# PowerSwitch.net
KiCad netlist of a schematic drawn in Altium Designer
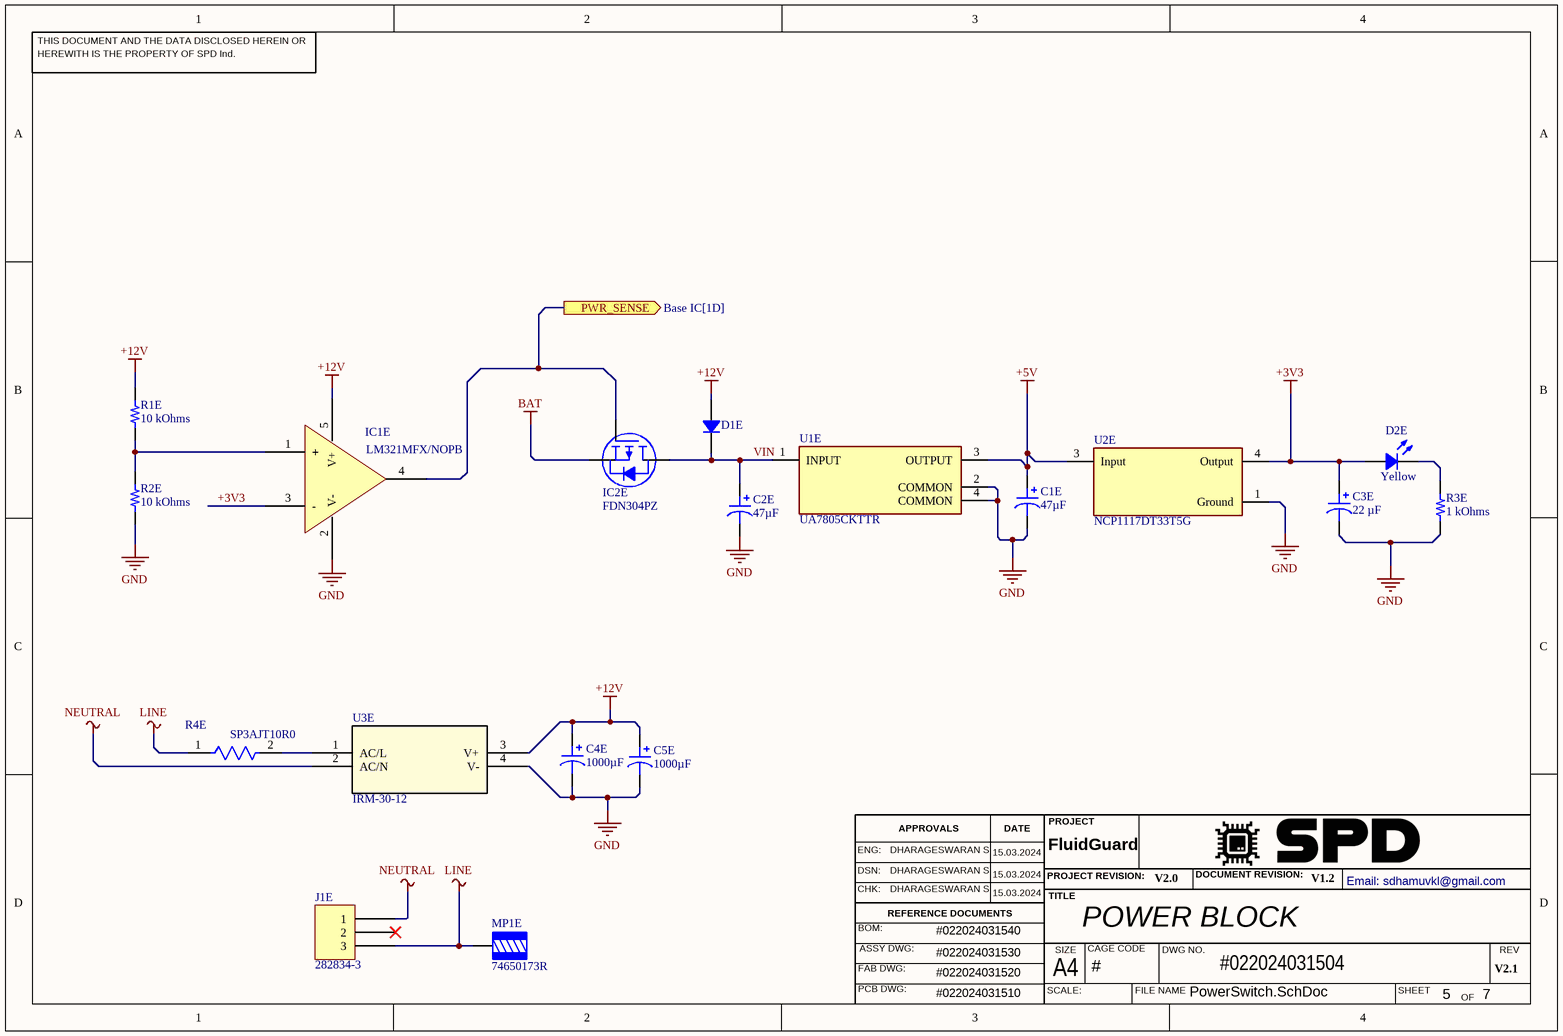
[diagram p0: PowerSwitch.SchDoc]

(export (version "E")
  (design (tool "Eeschema 10.0.6"))
  (components
    (comp (ref "C1E")
      (value "47µF")
      (footprint "CAP ALSMD 6.6MM H5.4MM")
      (description "CAP ALUM 47UF 20% 16V SMD")
      (fields
        (field (name "PART NUMBER") "EEE-HA1C470P")
        (field (name "MANUFACTURER") "Panasonic Electronic Components")
      )
      (libsource (lib "Postgres Altium Library - altium_library") (part "Polarised Capacitor"))
    )
    (comp (ref "C2E")
      (value "47µF")
      (footprint "CAP ALSMD 6.6MM H5.4MM")
      (description "CAP ALUM 47UF 20% 16V SMD")
      (fields
        (field (name "PART NUMBER") "EEE-HA1C470P")
        (field (name "MANUFACTURER") "Panasonic Electronic Components")
      )
      (libsource (lib "Postgres Altium Library - altium_library") (part "Polarised Capacitor"))
    )
    (comp (ref "C3E")
      (value "22 µF")
      (footprint "CAP POL 2917_7343")
      (description "CAP TANT 22UF 10% 10V 2917")
      (fields (field (name "PART NUMBER") "T491D226K010AT") (field (name "MANUFACTURER") "KEMET"))
      (libsource (lib "Postgres Altium Library - altium_library") (part "Polarised Capacitor"))
    )
    (comp (ref "C4E")
      (value "1000µF")
      (footprint "CAP TH ALUM ELEC D10.00mm S5.00mm H14.00mm")
      (description "CAP ALUM 1000UF 20% 16V RADIAL")
      (fields (field (name "PART NUMBER") "860020375017") (field (name "MANUFACTURER") "Würth Elektronik"))
      (libsource (lib "Postgres Altium Library - altium_library") (part "Polarised Capacitor"))
    )
    (comp (ref "C5E")
      (value "1000µF")
      (footprint "CAP TH ALUM ELEC D10.00mm S5.00mm H14.00mm")
      (description "CAP ALUM 1000UF 20% 16V RADIAL")
      (fields (field (name "PART NUMBER") "860020375017") (field (name "MANUFACTURER") "Würth Elektronik"))
      (libsource (lib "Postgres Altium Library - altium_library") (part "Polarised Capacitor"))
    )
    (comp (ref "D1E")
      (value "ES2A-13-F")
      (footprint "DO214AA SMB")
      (description "DIODE GEN PURP 50V 2A SMB")
      (fields (field (name "MANUFACTURER") "Diodes Incorporated"))
      (libsource (lib "Postgres Altium Library - altium_library") (part "Diode"))
    )
    (comp (ref "D2E")
      (value "Yellow")
      (footprint "LED 0402_1005 YELLOW")
      (description "LED YELLOW CLEAR 0402 SMD")
      (fields (field (name "PART NUMBER") "SM0402YC") (field (name "MANUFACTURER") "Bivar Inc."))
      (libsource (lib "Postgres Altium Library - altium_library") (part "LED"))
    )
    (comp (ref "IC1E")
      (value "LM321MFX/NOPB")
      (footprint "TI SOT-23-5 DBV")
      (description "IC OPAMP GP 1 CIRCUIT SOT23-5")
      (fields (field (name "MANUFACTURER") "Texas Instruments"))
      (libsource (lib "Postgres Altium Library - altium_library") (part "TI LM321"))
    )
    (comp (ref "IC2E")
      (value "FDN304PZ")
      (footprint "ON SEMI SOT-23-3")
      (description "MOSFET P-CH 20V 2.4A SSOT-3")
      (fields (field (name "MANUFACTURER") "ON Semiconductor"))
      (libsource (lib "Postgres Altium Library - altium_library") (part "ON SEMI MOSFET P-CH SOT-23-3"))
    )
    (comp (ref "J1E")
      (value "282834-3")
      (footprint "TE 282834-3")
      (description "TERM BLK 3P SIDE ENT 2.54MM PCB")
      (fields (field (name "VOLTAGE") "150V") (field (name "MANUFACTURER") "TE Connectivity AMP Connectors"))
      (libsource (lib "Postgres Altium Library - altium_library") (part "3 Pin"))
    )
    (comp (ref "MP1E")
      (value "74650173R")
      (footprint "WURTH 74650173")
      (description "TERM REDCUBE M3 4PIN PCB")
      (fields (field (name "MANUFACTURER") "Würth Elektronik"))
      (libsource (lib "Postgres Altium Library - altium_library") (part "MOUNTING POINT"))
    )
    (comp (ref "R1E")
      (value "10 kOhms")
      (footprint "RES 0402_1005")
      (description "RES SMD 10K OHM 1% 1/16W 0402")
      (fields (field (name "PART NUMBER") "AA0402FR-0710KL") (field (name "TOLERANCE") "±1%"))
      (libsource (lib "Postgres Altium Library - altium_library") (part "Resistor"))
    )
    (comp (ref "R2E")
      (value "10 kOhms")
      (footprint "RES 0402_1005")
      (description "RES SMD 10K OHM 1% 1/16W 0402")
      (fields (field (name "PART NUMBER") "AA0402FR-0710KL") (field (name "TOLERANCE") "±1%"))
      (libsource (lib "Postgres Altium Library - altium_library") (part "Resistor"))
    )
    (comp (ref "R3E")
      (value "1 kOhms")
      (footprint "RES 0402_1005")
      (description "RES SMD 1K OHM 1% 1/16W 0402")
      (fields (field (name "PART NUMBER") "AA0402FR-071KL") (field (name "TOLERANCE") "±1%"))
      (libsource (lib "Postgres Altium Library - altium_library") (part "Resistor"))
    )
    (comp (ref "R4E")
      (value "SP3AJT10R0")
      (footprint "FP-SP3A-MFG")
      (description "RES 10 OHM 5% 4W AXIAL")
      (fields (field (name "TOLERANCE") "5%"))
      (libsource (lib "Altium Content Vault") (part "1029c3af85768c4190bb7ad29bc67b5"))
    )
    (comp (ref "U1E")
      (value "UA7805CKTTR")
      (footprint "FP-KTT0003A-MFG")
      (description "IC REG LIN 5V 1.5A DDPAK/TO263-3")
      (libsource (lib "Altium Content Vault") (part "ebcbf24666fa34e59130a841f5280a4"))
    )
    (comp (ref "U2E")
      (value "NCP1117DT33T5G")
      (footprint "FP-369C-MFG")
      (description "IC REG LINEAR 3.3V 1A DPAK")
      (libsource (lib "Altium Content Vault") (part "f1512ae604efdd4bd306cab1b45f420"))
    )
    (comp (ref "U3E")
      (value "IRM-30-12")
      (footprint "IRM-30_MWU")
      (description "No Description Available")
      (libsource (lib "IRM-30-12") (part "IRM-30-12"))
    )
  )
  (nets
    (net (code "1") (name "+3V3") (class "Default")
      (node (ref "C3E") (pin "1") (pinfunction "1_1") (pintype "passive"))
      (node (ref "D2E") (pin "1") (pinfunction "1_1") (pintype "passive"))
      (node (ref "IC1E") (pin "3") (pinfunction "-_3") (pintype "passive"))
      (node (ref "U2E") (pin "4") (pinfunction "Output_4") (pintype "power_in"))
    )
    (net (code "2") (name "+5V") (class "Default")
      (node (ref "C1E") (pin "1") (pinfunction "1_1") (pintype "passive"))
      (node (ref "U1E") (pin "3") (pinfunction "OUTPUT_3") (pintype "power_in"))
      (node (ref "U2E") (pin "3") (pinfunction "Input_3") (pintype "power_in"))
    )
    (net (code "3") (name "+12V") (class "Default")
      (node (ref "C4E") (pin "1") (pinfunction "1_1") (pintype "passive"))
      (node (ref "C5E") (pin "1") (pinfunction "1_1") (pintype "passive"))
      (node (ref "D1E") (pin "1") (pinfunction "1_1") (pintype "passive"))
      (node (ref "IC1E") (pin "5") (pinfunction "V+_5") (pintype "passive"))
      (node (ref "R1E") (pin "2") (pinfunction "2_2") (pintype "passive"))
      (node (ref "U3E") (pin "3") (pinfunction "V+_3") (pintype "power_in"))
    )
    (net (code "4") (name "/PWR_SENSE") (class "Default")
      (node (ref "IC1E") (pin "4") (pinfunction "OUT_4") (pintype "passive"))
      (node (ref "IC2E") (pin "1") (pinfunction "G_1") (pintype "passive"))
    )
    (net (code "5") (name "/VIN") (class "Default")
      (node (ref "C2E") (pin "1") (pinfunction "1_1") (pintype "passive"))
      (node (ref "D1E") (pin "2") (pinfunction "2_2") (pintype "passive"))
      (node (ref "IC2E") (pin "3") (pinfunction "D_3") (pintype "passive"))
      (node (ref "U1E") (pin "1") (pinfunction "INPUT_1") (pintype "power_in"))
    )
    (net (code "6") (name "BAT") (class "Default")
      (node (ref "IC2E") (pin "2") (pinfunction "S_2") (pintype "passive"))
    )
    (net (code "7") (name "GND") (class "Default")
      (node (ref "C1E") (pin "2") (pinfunction "2_2") (pintype "passive"))
      (node (ref "C2E") (pin "2") (pinfunction "2_2") (pintype "passive"))
      (node (ref "C3E") (pin "2") (pinfunction "2_2") (pintype "passive"))
      (node (ref "C4E") (pin "2") (pinfunction "2_2") (pintype "passive"))
      (node (ref "C5E") (pin "2") (pinfunction "2_2") (pintype "passive"))
      (node (ref "IC1E") (pin "2") (pinfunction "V-_2") (pintype "passive"))
      (node (ref "R2E") (pin "1") (pinfunction "1_1") (pintype "passive"))
      (node (ref "R3E") (pin "1") (pinfunction "1_1") (pintype "passive"))
      (node (ref "U1E") (pin "2") (pinfunction "COMMON_2") (pintype "power_in"))
      (node (ref "U1E") (pin "4") (pinfunction "COMMON_4") (pintype "power_in"))
      (node (ref "U2E") (pin "1") (pinfunction "Ground_1") (pintype "power_in"))
      (node (ref "U3E") (pin "4") (pinfunction "V-_4") (pintype "power_in"))
    )
    (net (code "8") (name "LINE") (class "Default")
      (node (ref "J1E") (pin "3") (pinfunction "3_3") (pintype "passive"))
      (node (ref "MP1E") (pin "1") (pinfunction "1_1") (pintype "passive"))
      (node (ref "R4E") (pin "1") (pinfunction "1_1") (pintype "passive"))
    )
    (net (code "9") (name "NEUTRAL") (class "Default")
      (node (ref "J1E") (pin "1") (pinfunction "1_1") (pintype "passive"))
      (node (ref "U3E") (pin "2") (pinfunction "AC/N_2") (pintype "passive"))
    )
    (net (code "10") (name "Net-(D2E-Pad2)") (class "Default")
      (node (ref "D2E") (pin "2") (pinfunction "2_2") (pintype "passive"))
      (node (ref "R3E") (pin "2") (pinfunction "2_2") (pintype "passive"))
    )
    (net (code "11") (name "Net-(IC1E-+)") (class "Default")
      (node (ref "IC1E") (pin "1") (pinfunction "+_1") (pintype "passive"))
      (node (ref "R1E") (pin "1") (pinfunction "1_1") (pintype "passive"))
      (node (ref "R2E") (pin "2") (pinfunction "2_2") (pintype "passive"))
    )
    (net (code "12") (name "Net-(U3E-AC{slash}L)") (class "Default")
      (node (ref "R4E") (pin "2") (pinfunction "2_2") (pintype "passive"))
      (node (ref "U3E") (pin "1") (pinfunction "AC/L_1") (pintype "passive"))
    )
    (net (code "13") (name "unconnected-(J1E-Pad2)") (class "Default")
      (node (ref "J1E") (pin "2") (pinfunction "2_2") (pintype "passive+no_connect"))
    )
  )
)
